# SHDN21-S02-V00-SegInterface.net
KiCad netlist of a schematic drawn in Altium Designer
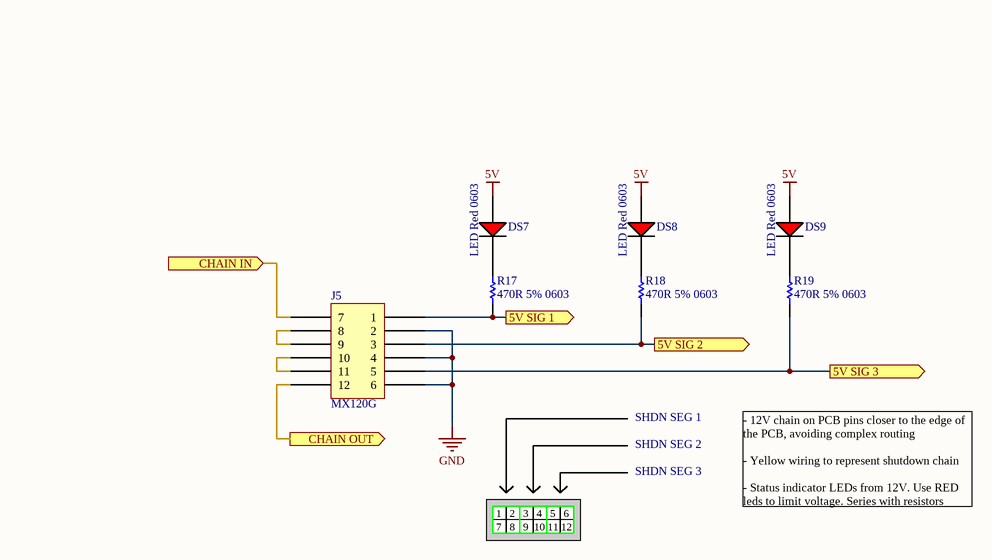
[diagram p0: SHDN21-S02-V00-SegInterface.SchDoc]

(export (version "E")
  (design (tool "Eeschema 10.0.6"))
  (components
    (comp (ref "DS7")
      (value "LED Red 0603")
      (footprint "LED RED 0603")
      (libsource (lib "QUTMS_LEDLibrary") (part "LED Red 0603"))
    )
    (comp (ref "DS8")
      (value "LED Red 0603")
      (footprint "LED RED 0603")
      (libsource (lib "QUTMS_LEDLibrary") (part "LED Red 0603"))
    )
    (comp (ref "DS9")
      (value "LED Red 0603")
      (footprint "LED RED 0603")
      (libsource (lib "QUTMS_LEDLibrary") (part "LED Red 0603"))
    )
    (comp (ref "J5")
      (value "MX120G")
      (description "MX120G with standard connector layout")
      (libsource (lib "QUTMS_MolexLibrary") (part "MX120G"))
    )
    (comp (ref "R17")
      (value "470R 5% 0603")
      (footprint "Res_ThinFilm_0603")
      (description "Resistor, SMD, 470R, 0.1W, 5%, 0603")
      (libsource (lib "StandardResistors") (part "470R 5% 0603"))
    )
    (comp (ref "R18")
      (value "470R 5% 0603")
      (footprint "Res_ThinFilm_0603")
      (description "Resistor, SMD, 470R, 0.1W, 5%, 0603")
      (libsource (lib "StandardResistors") (part "470R 5% 0603"))
    )
    (comp (ref "R19")
      (value "470R 5% 0603")
      (footprint "Res_ThinFilm_0603")
      (description "Resistor, SMD, 470R, 0.1W, 5%, 0603")
      (libsource (lib "StandardResistors") (part "470R 5% 0603"))
    )
  )
  (nets
    (net (code "1") (name "/5V SIG 1") (class "Default")
      (node (ref "J5") (pin "1") (pinfunction "1_1") (pintype "passive"))
      (node (ref "R17") (pin "1") (pinfunction "1_1") (pintype "passive"))
    )
    (net (code "2") (name "/5V SIG 2") (class "Default")
      (node (ref "J5") (pin "3") (pinfunction "3_3") (pintype "passive"))
      (node (ref "R18") (pin "1") (pinfunction "1_1") (pintype "passive"))
    )
    (net (code "3") (name "/5V SIG 3") (class "Default")
      (node (ref "J5") (pin "5") (pinfunction "5_5") (pintype "passive"))
      (node (ref "R19") (pin "1") (pinfunction "1_1") (pintype "passive"))
    )
    (net (code "4") (name "/CHAIN IN") (class "Default")
      (node (ref "J5") (pin "7") (pinfunction "7_7") (pintype "passive"))
    )
    (net (code "5") (name "/CHAIN OUT") (class "Default")
      (node (ref "J5") (pin "12") (pinfunction "12_12") (pintype "passive"))
    )
    (net (code "6") (name "5V") (class "Default")
      (node (ref "DS7") (pin "1") (pinfunction "A_1") (pintype "passive"))
      (node (ref "DS8") (pin "1") (pinfunction "A_1") (pintype "passive"))
      (node (ref "DS9") (pin "1") (pinfunction "A_1") (pintype "passive"))
    )
    (net (code "7") (name "GND") (class "Default")
      (node (ref "J5") (pin "2") (pinfunction "2_2") (pintype "passive"))
      (node (ref "J5") (pin "4") (pinfunction "4_4") (pintype "passive"))
      (node (ref "J5") (pin "6") (pinfunction "6_6") (pintype "passive"))
    )
    (net (code "8") (name "Net-(DS7-C)") (class "Default")
      (node (ref "DS7") (pin "2") (pinfunction "C_2") (pintype "passive"))
      (node (ref "R17") (pin "2") (pinfunction "2_2") (pintype "passive"))
    )
    (net (code "9") (name "Net-(DS8-C)") (class "Default")
      (node (ref "DS8") (pin "2") (pinfunction "C_2") (pintype "passive"))
      (node (ref "R18") (pin "2") (pinfunction "2_2") (pintype "passive"))
    )
    (net (code "10") (name "Net-(DS9-C)") (class "Default")
      (node (ref "DS9") (pin "2") (pinfunction "C_2") (pintype "passive"))
      (node (ref "R19") (pin "2") (pinfunction "2_2") (pintype "passive"))
    )
    (net (code "11") (name "Net-(J5-Pad8)") (class "Default")
      (node (ref "J5") (pin "8") (pinfunction "8_8") (pintype "passive"))
      (node (ref "J5") (pin "9") (pinfunction "9_9") (pintype "passive"))
    )
    (net (code "12") (name "Net-(J5-Pad10)") (class "Default")
      (node (ref "J5") (pin "10") (pinfunction "10_10") (pintype "passive"))
      (node (ref "J5") (pin "11") (pinfunction "11_11") (pintype "passive"))
    )
  )
)
